# 05.net
KiCad netlist of a schematic drawn in Altium Designer
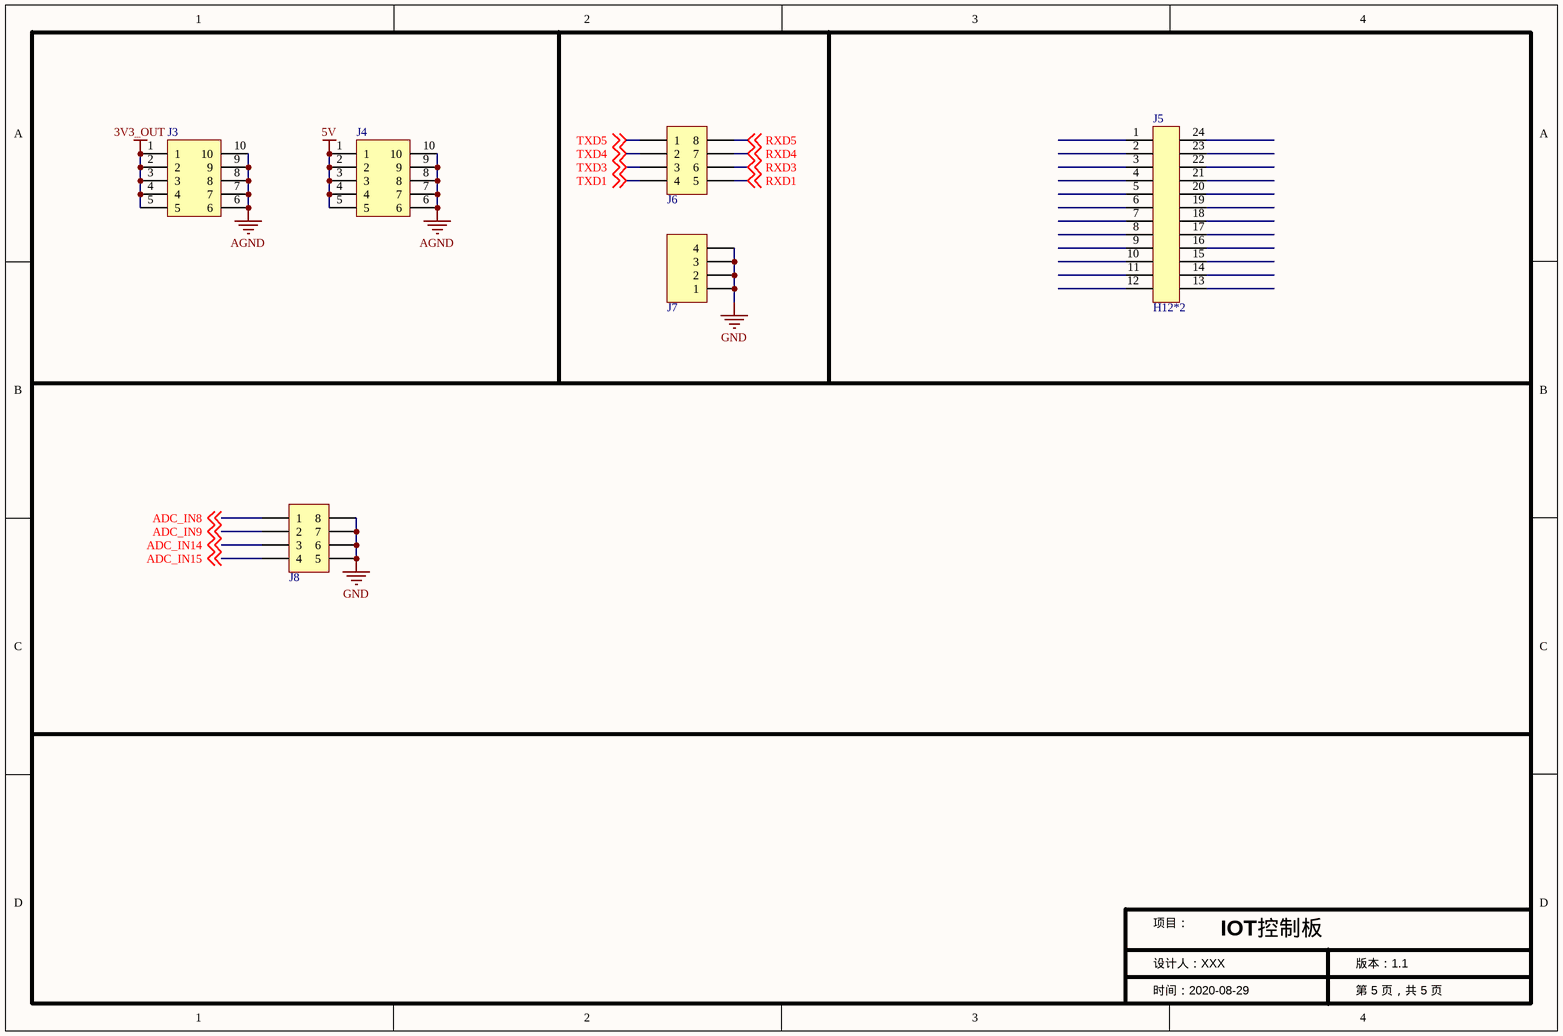
[diagram p0: 05_信号驱动部分.SchDoc]

(export (version "E")
  (design (tool "Eeschema 10.0.6"))
  (components
    (comp (ref "J3")
      (value "Header_5X2")
      (footprint "Header_5X2_2.54_排针")
      (description "接插件")
      (libsource (lib "Arrowy_Racing") (part "Header_5X2"))
    )
    (comp (ref "J4")
      (value "Header_5X2")
      (footprint "Header_5X2_2.54_排针")
      (description "接插件")
      (libsource (lib "Arrowy_Racing") (part "Header_5X2"))
    )
    (comp (ref "J5") (value "H12*2") (footprint "H12*2") (libsource (lib "Arrowy_Racing") (part "H12*2")))
    (comp (ref "J6")
      (value "Header_4X2")
      (footprint "Header_4x2-2.54")
      (description "接插件")
      (fields (field (name "PUBLISHER") "Altium Limited"))
      (libsource (lib "Arrowy_Racing") (part "Header_4X2"))
    )
    (comp (ref "J7")
      (value "Header 4")
      (footprint "Header_4X1_2.54_排针")
      (description "接插件")
      (fields (field (name "PUBLISHER") "Altium Limited"))
      (libsource (lib "Arrowy_Racing") (part "Header 4"))
    )
    (comp (ref "J8")
      (value "Header_4X2")
      (footprint "Header_4x2-2.54")
      (description "接插件")
      (fields (field (name "PUBLISHER") "Altium Limited"))
      (libsource (lib "Arrowy_Racing") (part "Header_4X2"))
    )
  )
  (nets
    (net (code "1") (name "3V3_OUT") (class "Default")
      (node (ref "J3") (pin "1") (pinfunction "1_1") (pintype "passive"))
      (node (ref "J3") (pin "2") (pinfunction "2_2") (pintype "passive"))
      (node (ref "J3") (pin "3") (pinfunction "3_3") (pintype "passive"))
      (node (ref "J3") (pin "4") (pinfunction "4_4") (pintype "passive"))
      (node (ref "J3") (pin "5") (pinfunction "5_5") (pintype "passive"))
    )
    (net (code "2") (name "5V") (class "Default")
      (node (ref "J4") (pin "1") (pinfunction "1_1") (pintype "passive"))
      (node (ref "J4") (pin "2") (pinfunction "2_2") (pintype "passive"))
      (node (ref "J4") (pin "3") (pinfunction "3_3") (pintype "passive"))
      (node (ref "J4") (pin "4") (pinfunction "4_4") (pintype "passive"))
      (node (ref "J4") (pin "5") (pinfunction "5_5") (pintype "passive"))
    )
    (net (code "3") (name "ADC_IN8") (class "Default")
      (node (ref "J8") (pin "1") (pinfunction "1_1") (pintype "passive"))
    )
    (net (code "4") (name "ADC_IN9") (class "Default")
      (node (ref "J8") (pin "2") (pinfunction "2_2") (pintype "passive"))
    )
    (net (code "5") (name "ADC_IN14") (class "Default")
      (node (ref "J8") (pin "3") (pinfunction "3_3") (pintype "passive"))
    )
    (net (code "6") (name "ADC_IN15") (class "Default")
      (node (ref "J8") (pin "4") (pinfunction "4_4") (pintype "passive"))
    )
    (net (code "7") (name "AGND") (class "Default")
      (node (ref "J3") (pin "10") (pinfunction "10_10") (pintype "passive"))
      (node (ref "J3") (pin "6") (pinfunction "6_6") (pintype "passive"))
      (node (ref "J3") (pin "7") (pinfunction "7_7") (pintype "passive"))
      (node (ref "J3") (pin "8") (pinfunction "8_8") (pintype "passive"))
      (node (ref "J3") (pin "9") (pinfunction "9_9") (pintype "passive"))
      (node (ref "J4") (pin "10") (pinfunction "10_10") (pintype "passive"))
      (node (ref "J4") (pin "6") (pinfunction "6_6") (pintype "passive"))
      (node (ref "J4") (pin "7") (pinfunction "7_7") (pintype "passive"))
      (node (ref "J4") (pin "8") (pinfunction "8_8") (pintype "passive"))
      (node (ref "J4") (pin "9") (pinfunction "9_9") (pintype "passive"))
    )
    (net (code "8") (name "GND") (class "Default")
      (node (ref "J7") (pin "1") (pinfunction "1_1") (pintype "passive"))
      (node (ref "J7") (pin "2") (pinfunction "2_2") (pintype "passive"))
      (node (ref "J7") (pin "3") (pinfunction "3_3") (pintype "passive"))
      (node (ref "J7") (pin "4") (pinfunction "4_4") (pintype "passive"))
      (node (ref "J8") (pin "5") (pinfunction "5_5") (pintype "passive"))
      (node (ref "J8") (pin "6") (pinfunction "6_6") (pintype "passive"))
      (node (ref "J8") (pin "7") (pinfunction "7_7") (pintype "passive"))
      (node (ref "J8") (pin "8") (pinfunction "8_8") (pintype "passive"))
    )
    (net (code "9") (name "RXD1") (class "Default")
      (node (ref "J6") (pin "5") (pinfunction "5_5") (pintype "passive"))
    )
    (net (code "10") (name "RXD3") (class "Default")
      (node (ref "J6") (pin "6") (pinfunction "6_6") (pintype "passive"))
    )
    (net (code "11") (name "RXD4") (class "Default")
      (node (ref "J6") (pin "7") (pinfunction "7_7") (pintype "passive"))
    )
    (net (code "12") (name "RXD5") (class "Default")
      (node (ref "J6") (pin "8") (pinfunction "8_8") (pintype "passive"))
    )
    (net (code "13") (name "TXD1") (class "Default")
      (node (ref "J6") (pin "4") (pinfunction "4_4") (pintype "passive"))
    )
    (net (code "14") (name "TXD3") (class "Default")
      (node (ref "J6") (pin "3") (pinfunction "3_3") (pintype "passive"))
    )
    (net (code "15") (name "TXD4") (class "Default")
      (node (ref "J6") (pin "2") (pinfunction "2_2") (pintype "passive"))
    )
    (net (code "16") (name "TXD5") (class "Default")
      (node (ref "J6") (pin "1") (pinfunction "1_1") (pintype "passive"))
    )
    (net (code "17") (name "unconnected-(J5-Pad1)") (class "Default")
      (node (ref "J5") (pin "1") (pinfunction "1_1") (pintype "passive"))
    )
    (net (code "18") (name "unconnected-(J5-Pad2)") (class "Default")
      (node (ref "J5") (pin "2") (pinfunction "2_2") (pintype "passive"))
    )
    (net (code "19") (name "unconnected-(J5-Pad3)") (class "Default")
      (node (ref "J5") (pin "3") (pinfunction "3_3") (pintype "passive"))
    )
    (net (code "20") (name "unconnected-(J5-Pad4)") (class "Default")
      (node (ref "J5") (pin "4") (pinfunction "4_4") (pintype "passive"))
    )
    (net (code "21") (name "unconnected-(J5-Pad5)") (class "Default")
      (node (ref "J5") (pin "5") (pinfunction "5_5") (pintype "passive"))
    )
    (net (code "22") (name "unconnected-(J5-Pad6)") (class "Default")
      (node (ref "J5") (pin "6") (pinfunction "6_6") (pintype "passive"))
    )
    (net (code "23") (name "unconnected-(J5-Pad7)") (class "Default")
      (node (ref "J5") (pin "7") (pinfunction "7_7") (pintype "passive"))
    )
    (net (code "24") (name "unconnected-(J5-Pad8)") (class "Default")
      (node (ref "J5") (pin "8") (pinfunction "8_8") (pintype "passive"))
    )
    (net (code "25") (name "unconnected-(J5-Pad9)") (class "Default")
      (node (ref "J5") (pin "9") (pinfunction "9_9") (pintype "passive"))
    )
    (net (code "26") (name "unconnected-(J5-Pad10)") (class "Default")
      (node (ref "J5") (pin "10") (pinfunction "10_10") (pintype "passive"))
    )
    (net (code "27") (name "unconnected-(J5-Pad11)") (class "Default")
      (node (ref "J5") (pin "11") (pinfunction "11_11") (pintype "passive"))
    )
    (net (code "28") (name "unconnected-(J5-Pad12)") (class "Default")
      (node (ref "J5") (pin "12") (pinfunction "12_12") (pintype "passive"))
    )
    (net (code "29") (name "unconnected-(J5-Pad13)") (class "Default")
      (node (ref "J5") (pin "13") (pinfunction "13_13") (pintype "passive"))
    )
    (net (code "30") (name "unconnected-(J5-Pad14)") (class "Default")
      (node (ref "J5") (pin "14") (pinfunction "14_14") (pintype "passive"))
    )
    (net (code "31") (name "unconnected-(J5-Pad15)") (class "Default")
      (node (ref "J5") (pin "15") (pinfunction "15_15") (pintype "passive"))
    )
    (net (code "32") (name "unconnected-(J5-Pad16)") (class "Default")
      (node (ref "J5") (pin "16") (pinfunction "16_16") (pintype "passive"))
    )
    (net (code "33") (name "unconnected-(J5-Pad17)") (class "Default")
      (node (ref "J5") (pin "17") (pinfunction "17_17") (pintype "passive"))
    )
    (net (code "34") (name "unconnected-(J5-Pad18)") (class "Default")
      (node (ref "J5") (pin "18") (pinfunction "18_18") (pintype "passive"))
    )
    (net (code "35") (name "unconnected-(J5-Pad19)") (class "Default")
      (node (ref "J5") (pin "19") (pinfunction "19_19") (pintype "passive"))
    )
    (net (code "36") (name "unconnected-(J5-Pad20)") (class "Default")
      (node (ref "J5") (pin "20") (pinfunction "20_20") (pintype "passive"))
    )
    (net (code "37") (name "unconnected-(J5-Pad21)") (class "Default")
      (node (ref "J5") (pin "21") (pinfunction "21_21") (pintype "passive"))
    )
    (net (code "38") (name "unconnected-(J5-Pad22)") (class "Default")
      (node (ref "J5") (pin "22") (pinfunction "22_22") (pintype "passive"))
    )
    (net (code "39") (name "unconnected-(J5-Pad23)") (class "Default")
      (node (ref "J5") (pin "23") (pinfunction "23_23") (pintype "passive"))
    )
    (net (code "40") (name "unconnected-(J5-Pad24)") (class "Default")
      (node (ref "J5") (pin "24") (pinfunction "24_24") (pintype "passive"))
    )
  )
)
